# SP_proto.net
KiCad netlist of a schematic drawn in EAGLE
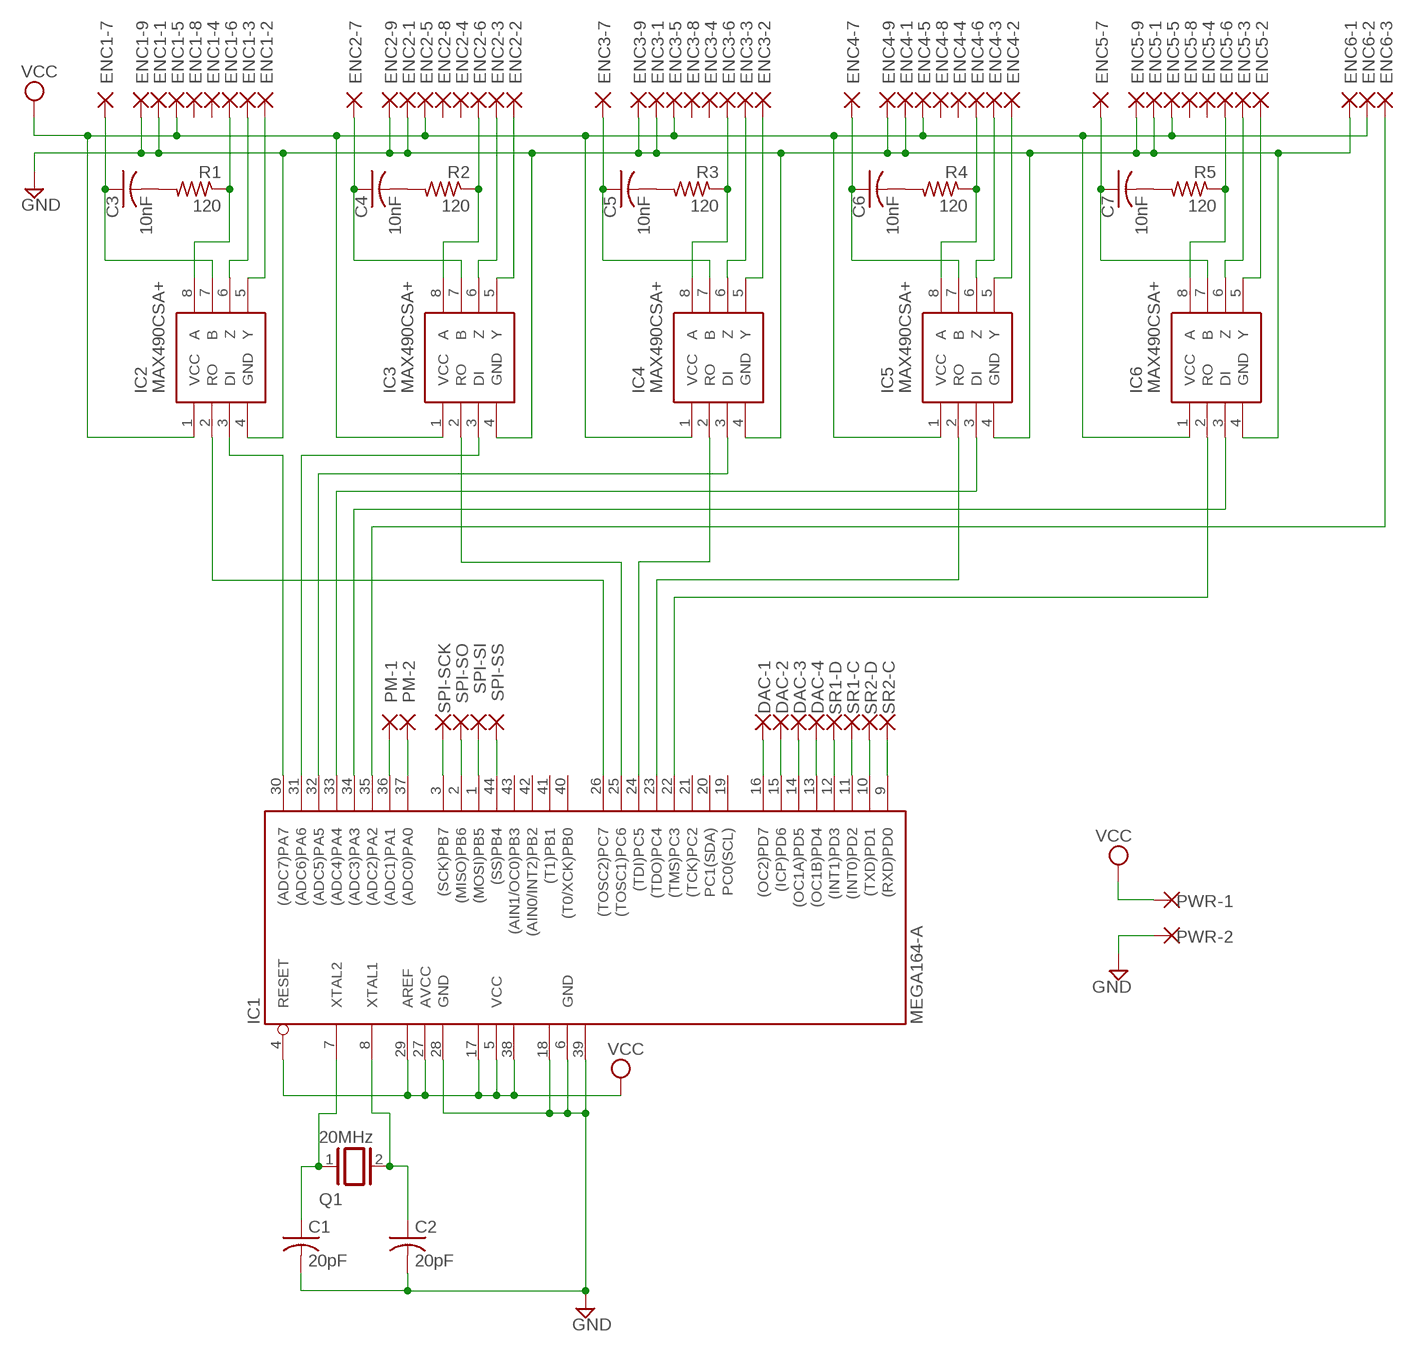
[diagram p0: schematic, sheet 1]

(export (version "E")
  (design (tool "Eeschema 10.0.6"))
  (components
    (comp (ref "C1")
      (value "20pF")
      (footprint "eagle-import:C050-024X044")
      (libsource (lib "eagle-import") (part "C-US050-024X044"))
    )
    (comp (ref "C2")
      (value "20pF")
      (footprint "eagle-import:C050-024X044")
      (libsource (lib "eagle-import") (part "C-US050-024X044"))
    )
    (comp (ref "C3")
      (value "10nF")
      (footprint "eagle-import:C050-024X044")
      (libsource (lib "eagle-import") (part "C-US050-024X044"))
    )
    (comp (ref "C4")
      (value "10nF")
      (footprint "eagle-import:C050-024X044")
      (libsource (lib "eagle-import") (part "C-US050-024X044"))
    )
    (comp (ref "C5")
      (value "10nF")
      (footprint "eagle-import:C050-024X044")
      (libsource (lib "eagle-import") (part "C-US050-024X044"))
    )
    (comp (ref "C6")
      (value "10nF")
      (footprint "eagle-import:C050-024X044")
      (libsource (lib "eagle-import") (part "C-US050-024X044"))
    )
    (comp (ref "C7")
      (value "10nF")
      (footprint "eagle-import:C050-024X044")
      (libsource (lib "eagle-import") (part "C-US050-024X044"))
    )
    (comp (ref "DAC-1")
      (value "1,6/0,8")
      (footprint "eagle-import:1,6_0,8")
      (libsource (lib "eagle-import") (part "1,6/0,8"))
    )
    (comp (ref "DAC-2")
      (value "1,6/0,8")
      (footprint "eagle-import:1,6_0,8")
      (libsource (lib "eagle-import") (part "1,6/0,8"))
    )
    (comp (ref "DAC-3")
      (value "1,6/0,8")
      (footprint "eagle-import:1,6_0,8")
      (libsource (lib "eagle-import") (part "1,6/0,8"))
    )
    (comp (ref "DAC-4")
      (value "1,6/0,8")
      (footprint "eagle-import:1,6_0,8")
      (libsource (lib "eagle-import") (part "1,6/0,8"))
    )
    (comp (ref "ENC1-1")
      (value "1,6/0,8")
      (footprint "eagle-import:1,6_0,8")
      (libsource (lib "eagle-import") (part "1,6/0,8"))
    )
    (comp (ref "ENC1-2")
      (value "1,6/0,8")
      (footprint "eagle-import:1,6_0,8")
      (libsource (lib "eagle-import") (part "1,6/0,8"))
    )
    (comp (ref "ENC1-3")
      (value "1,6/0,8")
      (footprint "eagle-import:1,6_0,8")
      (libsource (lib "eagle-import") (part "1,6/0,8"))
    )
    (comp (ref "ENC1-4")
      (value "1,6/0,8")
      (footprint "eagle-import:1,6_0,8")
      (libsource (lib "eagle-import") (part "1,6/0,8"))
    )
    (comp (ref "ENC1-5")
      (value "1,6/0,8")
      (footprint "eagle-import:1,6_0,8")
      (libsource (lib "eagle-import") (part "1,6/0,8"))
    )
    (comp (ref "ENC1-6")
      (value "1,6/0,8")
      (footprint "eagle-import:1,6_0,8")
      (libsource (lib "eagle-import") (part "1,6/0,8"))
    )
    (comp (ref "ENC1-7")
      (value "1,6/0,8")
      (footprint "eagle-import:1,6_0,8")
      (libsource (lib "eagle-import") (part "1,6/0,8"))
    )
    (comp (ref "ENC1-8")
      (value "1,6/0,8")
      (footprint "eagle-import:1,6_0,8")
      (libsource (lib "eagle-import") (part "1,6/0,8"))
    )
    (comp (ref "ENC1-9")
      (value "1,6/0,8")
      (footprint "eagle-import:1,6_0,8")
      (libsource (lib "eagle-import") (part "1,6/0,8"))
    )
    (comp (ref "ENC2-1")
      (value "1,6/0,8")
      (footprint "eagle-import:1,6_0,8")
      (libsource (lib "eagle-import") (part "1,6/0,8"))
    )
    (comp (ref "ENC2-2")
      (value "1,6/0,8")
      (footprint "eagle-import:1,6_0,8")
      (libsource (lib "eagle-import") (part "1,6/0,8"))
    )
    (comp (ref "ENC2-3")
      (value "1,6/0,8")
      (footprint "eagle-import:1,6_0,8")
      (libsource (lib "eagle-import") (part "1,6/0,8"))
    )
    (comp (ref "ENC2-4")
      (value "1,6/0,8")
      (footprint "eagle-import:1,6_0,8")
      (libsource (lib "eagle-import") (part "1,6/0,8"))
    )
    (comp (ref "ENC2-5")
      (value "1,6/0,8")
      (footprint "eagle-import:1,6_0,8")
      (libsource (lib "eagle-import") (part "1,6/0,8"))
    )
    (comp (ref "ENC2-6")
      (value "1,6/0,8")
      (footprint "eagle-import:1,6_0,8")
      (libsource (lib "eagle-import") (part "1,6/0,8"))
    )
    (comp (ref "ENC2-7")
      (value "1,6/0,8")
      (footprint "eagle-import:1,6_0,8")
      (libsource (lib "eagle-import") (part "1,6/0,8"))
    )
    (comp (ref "ENC2-8")
      (value "1,6/0,8")
      (footprint "eagle-import:1,6_0,8")
      (libsource (lib "eagle-import") (part "1,6/0,8"))
    )
    (comp (ref "ENC2-9")
      (value "1,6/0,8")
      (footprint "eagle-import:1,6_0,8")
      (libsource (lib "eagle-import") (part "1,6/0,8"))
    )
    (comp (ref "ENC3-1")
      (value "1,6/0,8")
      (footprint "eagle-import:1,6_0,8")
      (libsource (lib "eagle-import") (part "1,6/0,8"))
    )
    (comp (ref "ENC3-2")
      (value "1,6/0,8")
      (footprint "eagle-import:1,6_0,8")
      (libsource (lib "eagle-import") (part "1,6/0,8"))
    )
    (comp (ref "ENC3-3")
      (value "1,6/0,8")
      (footprint "eagle-import:1,6_0,8")
      (libsource (lib "eagle-import") (part "1,6/0,8"))
    )
    (comp (ref "ENC3-4")
      (value "1,6/0,8")
      (footprint "eagle-import:1,6_0,8")
      (libsource (lib "eagle-import") (part "1,6/0,8"))
    )
    (comp (ref "ENC3-5")
      (value "1,6/0,8")
      (footprint "eagle-import:1,6_0,8")
      (libsource (lib "eagle-import") (part "1,6/0,8"))
    )
    (comp (ref "ENC3-6")
      (value "1,6/0,8")
      (footprint "eagle-import:1,6_0,8")
      (libsource (lib "eagle-import") (part "1,6/0,8"))
    )
    (comp (ref "ENC3-7")
      (value "1,6/0,8")
      (footprint "eagle-import:1,6_0,8")
      (libsource (lib "eagle-import") (part "1,6/0,8"))
    )
    (comp (ref "ENC3-8")
      (value "1,6/0,8")
      (footprint "eagle-import:1,6_0,8")
      (libsource (lib "eagle-import") (part "1,6/0,8"))
    )
    (comp (ref "ENC3-9")
      (value "1,6/0,8")
      (footprint "eagle-import:1,6_0,8")
      (libsource (lib "eagle-import") (part "1,6/0,8"))
    )
    (comp (ref "ENC4-1")
      (value "1,6/0,8")
      (footprint "eagle-import:1,6_0,8")
      (libsource (lib "eagle-import") (part "1,6/0,8"))
    )
    (comp (ref "ENC4-2")
      (value "1,6/0,8")
      (footprint "eagle-import:1,6_0,8")
      (libsource (lib "eagle-import") (part "1,6/0,8"))
    )
    (comp (ref "ENC4-3")
      (value "1,6/0,8")
      (footprint "eagle-import:1,6_0,8")
      (libsource (lib "eagle-import") (part "1,6/0,8"))
    )
    (comp (ref "ENC4-4")
      (value "1,6/0,8")
      (footprint "eagle-import:1,6_0,8")
      (libsource (lib "eagle-import") (part "1,6/0,8"))
    )
    (comp (ref "ENC4-5")
      (value "1,6/0,8")
      (footprint "eagle-import:1,6_0,8")
      (libsource (lib "eagle-import") (part "1,6/0,8"))
    )
    (comp (ref "ENC4-6")
      (value "1,6/0,8")
      (footprint "eagle-import:1,6_0,8")
      (libsource (lib "eagle-import") (part "1,6/0,8"))
    )
    (comp (ref "ENC4-7")
      (value "1,6/0,8")
      (footprint "eagle-import:1,6_0,8")
      (libsource (lib "eagle-import") (part "1,6/0,8"))
    )
    (comp (ref "ENC4-8")
      (value "1,6/0,8")
      (footprint "eagle-import:1,6_0,8")
      (libsource (lib "eagle-import") (part "1,6/0,8"))
    )
    (comp (ref "ENC4-9")
      (value "1,6/0,8")
      (footprint "eagle-import:1,6_0,8")
      (libsource (lib "eagle-import") (part "1,6/0,8"))
    )
    (comp (ref "ENC5-1")
      (value "1,6/0,8")
      (footprint "eagle-import:1,6_0,8")
      (libsource (lib "eagle-import") (part "1,6/0,8"))
    )
    (comp (ref "ENC5-2")
      (value "1,6/0,8")
      (footprint "eagle-import:1,6_0,8")
      (libsource (lib "eagle-import") (part "1,6/0,8"))
    )
    (comp (ref "ENC5-3")
      (value "1,6/0,8")
      (footprint "eagle-import:1,6_0,8")
      (libsource (lib "eagle-import") (part "1,6/0,8"))
    )
    (comp (ref "ENC5-4")
      (value "1,6/0,8")
      (footprint "eagle-import:1,6_0,8")
      (libsource (lib "eagle-import") (part "1,6/0,8"))
    )
    (comp (ref "ENC5-5")
      (value "1,6/0,8")
      (footprint "eagle-import:1,6_0,8")
      (libsource (lib "eagle-import") (part "1,6/0,8"))
    )
    (comp (ref "ENC5-6")
      (value "1,6/0,8")
      (footprint "eagle-import:1,6_0,8")
      (libsource (lib "eagle-import") (part "1,6/0,8"))
    )
    (comp (ref "ENC5-7")
      (value "1,6/0,8")
      (footprint "eagle-import:1,6_0,8")
      (libsource (lib "eagle-import") (part "1,6/0,8"))
    )
    (comp (ref "ENC5-8")
      (value "1,6/0,8")
      (footprint "eagle-import:1,6_0,8")
      (libsource (lib "eagle-import") (part "1,6/0,8"))
    )
    (comp (ref "ENC5-9")
      (value "1,6/0,8")
      (footprint "eagle-import:1,6_0,8")
      (libsource (lib "eagle-import") (part "1,6/0,8"))
    )
    (comp (ref "ENC6-1")
      (value "1,6/0,8")
      (footprint "eagle-import:1,6_0,8")
      (libsource (lib "eagle-import") (part "1,6/0,8"))
    )
    (comp (ref "ENC6-2")
      (value "1,6/0,8")
      (footprint "eagle-import:1,6_0,8")
      (libsource (lib "eagle-import") (part "1,6/0,8"))
    )
    (comp (ref "ENC6-3")
      (value "1,6/0,8")
      (footprint "eagle-import:1,6_0,8")
      (libsource (lib "eagle-import") (part "1,6/0,8"))
    )
    (comp (ref "IC1")
      (value "MEGA164-A")
      (footprint "eagle-import:TQFP44")
      (fields (field (name "MPN") "ATMEGA16-16AU"))
      (libsource (lib "eagle-import") (part "MEGA16-A"))
    )
    (comp (ref "IC2")
      (value "MAX490CSA+")
      (footprint "eagle-import:SOIC127P600X175-8N")
      (fields (field (name "RS_PART_NUMBER") "6228181P"))
      (libsource (lib "eagle-import") (part "MAX490CSA+"))
    )
    (comp (ref "IC3")
      (value "MAX490CSA+")
      (footprint "eagle-import:SOIC127P600X175-8N")
      (fields (field (name "RS_PART_NUMBER") "6228181P"))
      (libsource (lib "eagle-import") (part "MAX490CSA+"))
    )
    (comp (ref "IC4")
      (value "MAX490CSA+")
      (footprint "eagle-import:SOIC127P600X175-8N")
      (fields (field (name "RS_PART_NUMBER") "6228181P"))
      (libsource (lib "eagle-import") (part "MAX490CSA+"))
    )
    (comp (ref "IC5")
      (value "MAX490CSA+")
      (footprint "eagle-import:SOIC127P600X175-8N")
      (fields (field (name "RS_PART_NUMBER") "6228181P"))
      (libsource (lib "eagle-import") (part "MAX490CSA+"))
    )
    (comp (ref "IC6")
      (value "MAX490CSA+")
      (footprint "eagle-import:SOIC127P600X175-8N")
      (fields (field (name "RS_PART_NUMBER") "6228181P"))
      (libsource (lib "eagle-import") (part "MAX490CSA+"))
    )
    (comp (ref "PM-1")
      (value "1,6/0,8")
      (footprint "eagle-import:1,6_0,8")
      (libsource (lib "eagle-import") (part "1,6/0,8"))
    )
    (comp (ref "PM-2")
      (value "1,6/0,8")
      (footprint "eagle-import:1,6_0,8")
      (libsource (lib "eagle-import") (part "1,6/0,8"))
    )
    (comp (ref "PWR-1")
      (value "1,6/0,8")
      (footprint "eagle-import:1,6_0,8")
      (libsource (lib "eagle-import") (part "1,6/0,8"))
    )
    (comp (ref "PWR-2")
      (value "1,6/0,8")
      (footprint "eagle-import:1,6_0,8")
      (libsource (lib "eagle-import") (part "1,6/0,8"))
    )
    (comp (ref "Q1")
      (value "20MHz")
      (footprint "eagle-import:QS")
      (libsource (lib "eagle-import") (part "XTAL/S"))
    )
    (comp (ref "R1")
      (value "120")
      (footprint "eagle-import:0204_7")
      (libsource (lib "eagle-import") (part "R-US_0204/7"))
    )
    (comp (ref "R2")
      (value "120")
      (footprint "eagle-import:0204_7")
      (libsource (lib "eagle-import") (part "R-US_0204/7"))
    )
    (comp (ref "R3")
      (value "120")
      (footprint "eagle-import:0204_7")
      (libsource (lib "eagle-import") (part "R-US_0204/7"))
    )
    (comp (ref "R4")
      (value "120")
      (footprint "eagle-import:0204_7")
      (libsource (lib "eagle-import") (part "R-US_0204/7"))
    )
    (comp (ref "R5")
      (value "120")
      (footprint "eagle-import:0204_7")
      (libsource (lib "eagle-import") (part "R-US_0204/7"))
    )
    (comp (ref "SPI-SCK")
      (value "1,6/0,8")
      (footprint "eagle-import:1,6_0,8")
      (libsource (lib "eagle-import") (part "1,6/0,8"))
    )
    (comp (ref "SPI-SI")
      (value "1,6/0,8")
      (footprint "eagle-import:1,6_0,8")
      (libsource (lib "eagle-import") (part "1,6/0,8"))
    )
    (comp (ref "SPI-SO")
      (value "1,6/0,8")
      (footprint "eagle-import:1,6_0,8")
      (libsource (lib "eagle-import") (part "1,6/0,8"))
    )
    (comp (ref "SPI-SS")
      (value "1,6/0,8")
      (footprint "eagle-import:1,6_0,8")
      (libsource (lib "eagle-import") (part "1,6/0,8"))
    )
    (comp (ref "SR1-C")
      (value "1,6/0,8")
      (footprint "eagle-import:1,6_0,8")
      (libsource (lib "eagle-import") (part "1,6/0,8"))
    )
    (comp (ref "SR1-D")
      (value "1,6/0,8")
      (footprint "eagle-import:1,6_0,8")
      (libsource (lib "eagle-import") (part "1,6/0,8"))
    )
    (comp (ref "SR2-C")
      (value "1,6/0,8")
      (footprint "eagle-import:1,6_0,8")
      (libsource (lib "eagle-import") (part "1,6/0,8"))
    )
    (comp (ref "SR2-D")
      (value "1,6/0,8")
      (footprint "eagle-import:1,6_0,8")
      (libsource (lib "eagle-import") (part "1,6/0,8"))
    )
  )
  (nets
    (net (code "1") (name "GND") (class "Default")
      (node (ref "C1") (pin "2") (pinfunction "2_2") (pintype "passive"))
      (node (ref "C2") (pin "2") (pinfunction "2_2") (pintype "passive"))
      (node (ref "ENC1-1") (pin "1") (pinfunction "P_1") (pintype "passive"))
      (node (ref "ENC1-9") (pin "1") (pinfunction "P_1") (pintype "passive"))
      (node (ref "ENC2-1") (pin "1") (pinfunction "P_1") (pintype "passive"))
      (node (ref "ENC2-9") (pin "1") (pinfunction "P_1") (pintype "passive"))
      (node (ref "ENC3-1") (pin "1") (pinfunction "P_1") (pintype "passive"))
      (node (ref "ENC3-9") (pin "1") (pinfunction "P_1") (pintype "passive"))
      (node (ref "ENC4-1") (pin "1") (pinfunction "P_1") (pintype "passive"))
      (node (ref "ENC4-9") (pin "1") (pinfunction "P_1") (pintype "passive"))
      (node (ref "ENC5-1") (pin "1") (pinfunction "P_1") (pintype "passive"))
      (node (ref "ENC5-9") (pin "1") (pinfunction "P_1") (pintype "passive"))
      (node (ref "ENC6-1") (pin "1") (pinfunction "P_1") (pintype "passive"))
      (node (ref "IC1") (pin "18") (pinfunction "GND1_18") (pintype "power_in"))
      (node (ref "IC1") (pin "28") (pinfunction "GND_28") (pintype "power_in"))
      (node (ref "IC1") (pin "39") (pinfunction "GND2_39") (pintype "power_in"))
      (node (ref "IC1") (pin "6") (pinfunction "GND_6") (pintype "power_in"))
      (node (ref "IC2") (pin "4") (pinfunction "GND_4") (pintype "power_in"))
      (node (ref "IC3") (pin "4") (pinfunction "GND_4") (pintype "power_in"))
      (node (ref "IC4") (pin "4") (pinfunction "GND_4") (pintype "power_in"))
      (node (ref "IC5") (pin "4") (pinfunction "GND_4") (pintype "power_in"))
      (node (ref "IC6") (pin "4") (pinfunction "GND_4") (pintype "power_in"))
      (node (ref "PWR-2") (pin "1") (pinfunction "P_1") (pintype "passive"))
    )
    (net (code "2") (name "Net-(C3-Pad2)") (class "Default")
      (node (ref "C3") (pin "2") (pinfunction "2_2") (pintype "passive"))
      (node (ref "R1") (pin "2") (pinfunction "2_2") (pintype "passive"))
    )
    (net (code "3") (name "Net-(C4-Pad2)") (class "Default")
      (node (ref "C4") (pin "2") (pinfunction "2_2") (pintype "passive"))
      (node (ref "R2") (pin "2") (pinfunction "2_2") (pintype "passive"))
    )
    (net (code "4") (name "Net-(C5-Pad2)") (class "Default")
      (node (ref "C5") (pin "2") (pinfunction "2_2") (pintype "passive"))
      (node (ref "R3") (pin "2") (pinfunction "2_2") (pintype "passive"))
    )
    (net (code "5") (name "Net-(C6-Pad2)") (class "Default")
      (node (ref "C6") (pin "2") (pinfunction "2_2") (pintype "passive"))
      (node (ref "R4") (pin "2") (pinfunction "2_2") (pintype "passive"))
    )
    (net (code "6") (name "Net-(C7-Pad2)") (class "Default")
      (node (ref "C7") (pin "2") (pinfunction "2_2") (pintype "passive"))
      (node (ref "R5") (pin "2") (pinfunction "2_2") (pintype "passive"))
    )
    (net (code "7") (name "Net-(DAC-1-P)") (class "Default")
      (node (ref "DAC-1") (pin "1") (pinfunction "P_1") (pintype "passive"))
      (node (ref "IC1") (pin "16") (pinfunction "(OC2)PD7_16") (pintype "bidirectional"))
    )
    (net (code "8") (name "Net-(DAC-2-P)") (class "Default")
      (node (ref "DAC-2") (pin "1") (pinfunction "P_1") (pintype "passive"))
      (node (ref "IC1") (pin "15") (pinfunction "(ICP)PD6_15") (pintype "bidirectional"))
    )
    (net (code "9") (name "Net-(DAC-3-P)") (class "Default")
      (node (ref "DAC-3") (pin "1") (pinfunction "P_1") (pintype "passive"))
      (node (ref "IC1") (pin "14") (pinfunction "(OC1A)PD5_14") (pintype "bidirectional"))
    )
    (net (code "10") (name "Net-(DAC-4-P)") (class "Default")
      (node (ref "DAC-4") (pin "1") (pinfunction "P_1") (pintype "passive"))
      (node (ref "IC1") (pin "13") (pinfunction "(OC1B)PD4_13") (pintype "bidirectional"))
    )
    (net (code "11") (name "Net-(ENC1-2-P)") (class "Default")
      (node (ref "ENC1-2") (pin "1") (pinfunction "P_1") (pintype "passive"))
      (node (ref "IC2") (pin "5") (pinfunction "Y_5") (pintype "bidirectional"))
    )
    (net (code "12") (name "Net-(ENC1-3-P)") (class "Default")
      (node (ref "ENC1-3") (pin "1") (pinfunction "P_1") (pintype "passive"))
      (node (ref "IC2") (pin "6") (pinfunction "Z_6") (pintype "bidirectional"))
    )
    (net (code "13") (name "Net-(ENC1-6-P)") (class "Default")
      (node (ref "ENC1-6") (pin "1") (pinfunction "P_1") (pintype "passive"))
      (node (ref "IC2") (pin "8") (pinfunction "A_8") (pintype "bidirectional"))
      (node (ref "R1") (pin "1") (pinfunction "1_1") (pintype "passive"))
    )
    (net (code "14") (name "Net-(ENC1-7-P)") (class "Default")
      (node (ref "C3") (pin "1") (pinfunction "1_1") (pintype "passive"))
      (node (ref "ENC1-7") (pin "1") (pinfunction "P_1") (pintype "passive"))
      (node (ref "IC2") (pin "7") (pinfunction "B_7") (pintype "bidirectional"))
    )
    (net (code "15") (name "Net-(ENC2-2-P)") (class "Default")
      (node (ref "ENC2-2") (pin "1") (pinfunction "P_1") (pintype "passive"))
      (node (ref "IC3") (pin "5") (pinfunction "Y_5") (pintype "bidirectional"))
    )
    (net (code "16") (name "Net-(ENC2-3-P)") (class "Default")
      (node (ref "ENC2-3") (pin "1") (pinfunction "P_1") (pintype "passive"))
      (node (ref "IC3") (pin "6") (pinfunction "Z_6") (pintype "bidirectional"))
    )
    (net (code "17") (name "Net-(ENC2-6-P)") (class "Default")
      (node (ref "ENC2-6") (pin "1") (pinfunction "P_1") (pintype "passive"))
      (node (ref "IC3") (pin "8") (pinfunction "A_8") (pintype "bidirectional"))
      (node (ref "R2") (pin "1") (pinfunction "1_1") (pintype "passive"))
    )
    (net (code "18") (name "Net-(ENC2-7-P)") (class "Default")
      (node (ref "C4") (pin "1") (pinfunction "1_1") (pintype "passive"))
      (node (ref "ENC2-7") (pin "1") (pinfunction "P_1") (pintype "passive"))
      (node (ref "IC3") (pin "7") (pinfunction "B_7") (pintype "bidirectional"))
    )
    (net (code "19") (name "Net-(ENC3-2-P)") (class "Default")
      (node (ref "ENC3-2") (pin "1") (pinfunction "P_1") (pintype "passive"))
      (node (ref "IC4") (pin "5") (pinfunction "Y_5") (pintype "bidirectional"))
    )
    (net (code "20") (name "Net-(ENC3-3-P)") (class "Default")
      (node (ref "ENC3-3") (pin "1") (pinfunction "P_1") (pintype "passive"))
      (node (ref "IC4") (pin "6") (pinfunction "Z_6") (pintype "bidirectional"))
    )
    (net (code "21") (name "Net-(ENC3-6-P)") (class "Default")
      (node (ref "ENC3-6") (pin "1") (pinfunction "P_1") (pintype "passive"))
      (node (ref "IC4") (pin "8") (pinfunction "A_8") (pintype "bidirectional"))
      (node (ref "R3") (pin "1") (pinfunction "1_1") (pintype "passive"))
    )
    (net (code "22") (name "Net-(ENC3-7-P)") (class "Default")
      (node (ref "C5") (pin "1") (pinfunction "1_1") (pintype "passive"))
      (node (ref "ENC3-7") (pin "1") (pinfunction "P_1") (pintype "passive"))
      (node (ref "IC4") (pin "7") (pinfunction "B_7") (pintype "bidirectional"))
    )
    (net (code "23") (name "Net-(ENC4-2-P)") (class "Default")
      (node (ref "ENC4-2") (pin "1") (pinfunction "P_1") (pintype "passive"))
      (node (ref "IC5") (pin "5") (pinfunction "Y_5") (pintype "bidirectional"))
    )
    (net (code "24") (name "Net-(ENC4-3-P)") (class "Default")
      (node (ref "ENC4-3") (pin "1") (pinfunction "P_1") (pintype "passive"))
      (node (ref "IC5") (pin "6") (pinfunction "Z_6") (pintype "bidirectional"))
    )
    (net (code "25") (name "Net-(ENC4-6-P)") (class "Default")
      (node (ref "ENC4-6") (pin "1") (pinfunction "P_1") (pintype "passive"))
      (node (ref "IC5") (pin "8") (pinfunction "A_8") (pintype "bidirectional"))
      (node (ref "R4") (pin "1") (pinfunction "1_1") (pintype "passive"))
    )
    (net (code "26") (name "Net-(ENC4-7-P)") (class "Default")
      (node (ref "C6") (pin "1") (pinfunction "1_1") (pintype "passive"))
      (node (ref "ENC4-7") (pin "1") (pinfunction "P_1") (pintype "passive"))
      (node (ref "IC5") (pin "7") (pinfunction "B_7") (pintype "bidirectional"))
    )
    (net (code "27") (name "Net-(ENC5-2-P)") (class "Default")
      (node (ref "ENC5-2") (pin "1") (pinfunction "P_1") (pintype "passive"))
      (node (ref "IC6") (pin "5") (pinfunction "Y_5") (pintype "bidirectional"))
    )
    (net (code "28") (name "Net-(ENC5-3-P)") (class "Default")
      (node (ref "ENC5-3") (pin "1") (pinfunction "P_1") (pintype "passive"))
      (node (ref "IC6") (pin "6") (pinfunction "Z_6") (pintype "bidirectional"))
    )
    (net (code "29") (name "Net-(ENC5-6-P)") (class "Default")
      (node (ref "ENC5-6") (pin "1") (pinfunction "P_1") (pintype "passive"))
      (node (ref "IC6") (pin "8") (pinfunction "A_8") (pintype "bidirectional"))
      (node (ref "R5") (pin "1") (pinfunction "1_1") (pintype "passive"))
    )
    (net (code "30") (name "Net-(ENC5-7-P)") (class "Default")
      (node (ref "C7") (pin "1") (pinfunction "1_1") (pintype "passive"))
      (node (ref "ENC5-7") (pin "1") (pinfunction "P_1") (pintype "passive"))
      (node (ref "IC6") (pin "7") (pinfunction "B_7") (pintype "bidirectional"))
    )
    (net (code "31") (name "Net-(ENC6-3-P)") (class "Default")
      (node (ref "ENC6-3") (pin "1") (pinfunction "P_1") (pintype "passive"))
      (node (ref "IC1") (pin "35") (pinfunction "(ADC2)PA2_35") (pintype "bidirectional"))
    )
    (net (code "32") (name "Net-(IC1-(ADC0)PA0)") (class "Default")
      (node (ref "IC1") (pin "37") (pinfunction "(ADC0)PA0_37") (pintype "bidirectional"))
      (node (ref "PM-2") (pin "1") (pinfunction "P_1") (pintype "passive"))
    )
    (net (code "33") (name "Net-(IC1-(ADC1)PA1)") (class "Default")
      (node (ref "IC1") (pin "36") (pinfunction "(ADC1)PA1_36") (pintype "bidirectional"))
      (node (ref "PM-1") (pin "1") (pinfunction "P_1") (pintype "passive"))
    )
    (net (code "34") (name "Net-(IC1-(ADC3)PA3)") (class "Default")
      (node (ref "IC1") (pin "34") (pinfunction "(ADC3)PA3_34") (pintype "bidirectional"))
      (node (ref "IC6") (pin "3") (pinfunction "DI_3") (pintype "bidirectional"))
    )
    (net (code "35") (name "Net-(IC1-(ADC4)PA4)") (class "Default")
      (node (ref "IC1") (pin "33") (pinfunction "(ADC4)PA4_33") (pintype "bidirectional"))
      (node (ref "IC5") (pin "3") (pinfunction "DI_3") (pintype "bidirectional"))
    )
    (net (code "36") (name "Net-(IC1-(ADC5)PA5)") (class "Default")
      (node (ref "IC1") (pin "32") (pinfunction "(ADC5)PA5_32") (pintype "bidirectional"))
      (node (ref "IC4") (pin "3") (pinfunction "DI_3") (pintype "bidirectional"))
    )
    (net (code "37") (name "Net-(IC1-(ADC6)PA6)") (class "Default")
      (node (ref "IC1") (pin "31") (pinfunction "(ADC6)PA6_31") (pintype "bidirectional"))
      (node (ref "IC3") (pin "3") (pinfunction "DI_3") (pintype "bidirectional"))
    )
    (net (code "38") (name "Net-(IC1-(ADC7)PA7)") (class "Default")
      (node (ref "IC1") (pin "30") (pinfunction "(ADC7)PA7_30") (pintype "bidirectional"))
      (node (ref "IC2") (pin "3") (pinfunction "DI_3") (pintype "bidirectional"))
    )
    (net (code "39") (name "Net-(IC1-(INT0)PD2)") (class "Default")
      (node (ref "IC1") (pin "11") (pinfunction "(INT0)PD2_11") (pintype "bidirectional"))
      (node (ref "SR1-C") (pin "1") (pinfunction "P_1") (pintype "passive"))
    )
    (net (code "40") (name "Net-(IC1-(INT1)PD3)") (class "Default")
      (node (ref "IC1") (pin "12") (pinfunction "(INT1)PD3_12") (pintype "bidirectional"))
      (node (ref "SR1-D") (pin "1") (pinfunction "P_1") (pintype "passive"))
    )
    (net (code "41") (name "Net-(IC1-(MISO)PB6)") (class "Default")
      (node (ref "IC1") (pin "2") (pinfunction "(MISO)PB6_2") (pintype "bidirectional"))
      (node (ref "SPI-SO") (pin "1") (pinfunction "P_1") (pintype "passive"))
    )
    (net (code "42") (name "Net-(IC1-(MOSI)PB5)") (class "Default")
      (node (ref "IC1") (pin "1") (pinfunction "(MOSI)PB5_1") (pintype "bidirectional"))
      (node (ref "SPI-SI") (pin "1") (pinfunction "P_1") (pintype "passive"))
    )
    (net (code "43") (name "Net-(IC1-(RXD)PD0)") (class "Default")
      (node (ref "IC1") (pin "9") (pinfunction "(RXD)PD0_9") (pintype "bidirectional"))
      (node (ref "SR2-C") (pin "1") (pinfunction "P_1") (pintype "passive"))
    )
    (net (code "44") (name "Net-(IC1-(SCK)PB7)") (class "Default")
      (node (ref "IC1") (pin "3") (pinfunction "(SCK)PB7_3") (pintype "bidirectional"))
      (node (ref "SPI-SCK") (pin "1") (pinfunction "P_1") (pintype "passive"))
    )
    (net (code "45") (name "Net-(IC1-(SS)PB4)") (class "Default")
      (node (ref "IC1") (pin "44") (pinfunction "(SS)PB4_44") (pintype "bidirectional"))
      (node (ref "SPI-SS") (pin "1") (pinfunction "P_1") (pintype "passive"))
    )
    (net (code "46") (name "Net-(IC1-(TDI)PC5)") (class "Default")
      (node (ref "IC1") (pin "24") (pinfunction "(TDI)PC5_24") (pintype "bidirectional"))
      (node (ref "IC4") (pin "2") (pinfunction "RO_2") (pintype "bidirectional"))
    )
    (net (code "47") (name "Net-(IC1-(TDO)PC4)") (class "Default")
      (node (ref "IC1") (pin "23") (pinfunction "(TDO)PC4_23") (pintype "bidirectional"))
      (node (ref "IC5") (pin "2") (pinfunction "RO_2") (pintype "bidirectional"))
    )
    (net (code "48") (name "Net-(IC1-(TMS)PC3)") (class "Default")
      (node (ref "IC1") (pin "22") (pinfunction "(TMS)PC3_22") (pintype "bidirectional"))
      (node (ref "IC6") (pin "2") (pinfunction "RO_2") (pintype "bidirectional"))
    )
    (net (code "49") (name "Net-(IC1-(TOSC1)PC6)") (class "Default")
      (node (ref "IC1") (pin "25") (pinfunction "(TOSC1)PC6_25") (pintype "bidirectional"))
      (node (ref "IC3") (pin "2") (pinfunction "RO_2") (pintype "bidirectional"))
    )
    (net (code "50") (name "Net-(IC1-(TOSC2)PC7)") (class "Default")
      (node (ref "IC1") (pin "26") (pinfunction "(TOSC2)PC7_26") (pintype "bidirectional"))
      (node (ref "IC2") (pin "2") (pinfunction "RO_2") (pintype "bidirectional"))
    )
    (net (code "51") (name "Net-(IC1-(TXD)PD1)") (class "Default")
      (node (ref "IC1") (pin "10") (pinfunction "(TXD)PD1_10") (pintype "bidirectional"))
      (node (ref "SR2-D") (pin "1") (pinfunction "P_1") (pintype "passive"))
    )
    (net (code "52") (name "Net-(IC1-XTAL1)") (class "Default")
      (node (ref "C2") (pin "1") (pinfunction "1_1") (pintype "passive"))
      (node (ref "IC1") (pin "8") (pinfunction "XTAL1_8") (pintype "bidirectional"))
      (node (ref "Q1") (pin "2") (pinfunction "2_2") (pintype "passive"))
    )
    (net (code "53") (name "Net-(IC1-XTAL2)") (class "Default")
      (node (ref "C1") (pin "1") (pinfunction "1_1") (pintype "passive"))
      (node (ref "IC1") (pin "7") (pinfunction "XTAL2_7") (pintype "bidirectional"))
      (node (ref "Q1") (pin "1") (pinfunction "1_1") (pintype "passive"))
    )
    (net (code "54") (name "VCC") (class "Default")
      (node (ref "ENC1-5") (pin "1") (pinfunction "P_1") (pintype "passive"))
      (node (ref "ENC2-5") (pin "1") (pinfunction "P_1") (pintype "passive"))
      (node (ref "ENC3-5") (pin "1") (pinfunction "P_1") (pintype "passive"))
      (node (ref "ENC4-5") (pin "1") (pinfunction "P_1") (pintype "passive"))
      (node (ref "ENC5-5") (pin "1") (pinfunction "P_1") (pintype "passive"))
      (node (ref "ENC6-2") (pin "1") (pinfunction "P_1") (pintype "passive"))
      (node (ref "IC1") (pin "17") (pinfunction "VCC1_17") (pintype "power_in"))
      (node (ref "IC1") (pin "27") (pinfunction "AVCC_27") (pintype "power_in"))
      (node (ref "IC1") (pin "29") (pinfunction "AREF_29") (pintype "passive"))
      (node (ref "IC1") (pin "38") (pinfunction "VCC2_38") (pintype "power_in"))
      (node (ref "IC1") (pin "4") (pinfunction "RESET_4") (pintype "input"))
      (node (ref "IC1") (pin "5") (pinfunction "VCC_5") (pintype "power_in"))
      (node (ref "IC2") (pin "1") (pinfunction "VCC_1") (pintype "power_in"))
      (node (ref "IC3") (pin "1") (pinfunction "VCC_1") (pintype "power_in"))
      (node (ref "IC4") (pin "1") (pinfunction "VCC_1") (pintype "power_in"))
      (node (ref "IC5") (pin "1") (pinfunction "VCC_1") (pintype "power_in"))
      (node (ref "IC6") (pin "1") (pinfunction "VCC_1") (pintype "power_in"))
      (node (ref "PWR-1") (pin "1") (pinfunction "P_1") (pintype "passive"))
    )
    (net (code "55") (name "unconnected-(ENC1-4-P-Pad1)") (class "Default")
      (node (ref "ENC1-4") (pin "1") (pinfunction "P_1") (pintype "passive"))
    )
    (net (code "56") (name "unconnected-(ENC1-8-P-Pad1)") (class "Default")
      (node (ref "ENC1-8") (pin "1") (pinfunction "P_1") (pintype "passive"))
    )
    (net (code "57") (name "unconnected-(ENC2-4-P-Pad1)") (class "Default")
      (node (ref "ENC2-4") (pin "1") (pinfunction "P_1") (pintype "passive"))
    )
    (net (code "58") (name "unconnected-(ENC2-8-P-Pad1)") (class "Default")
      (node (ref "ENC2-8") (pin "1") (pinfunction "P_1") (pintype "passive"))
    )
    (net (code "59") (name "unconnected-(ENC3-4-P-Pad1)") (class "Default")
      (node (ref "ENC3-4") (pin "1") (pinfunction "P_1") (pintype "passive"))
    )
    (net (code "60") (name "unconnected-(ENC3-8-P-Pad1)") (class "Default")
      (node (ref "ENC3-8") (pin "1") (pinfunction "P_1") (pintype "passive"))
    )
    (net (code "61") (name "unconnected-(ENC4-4-P-Pad1)") (class "Default")
      (node (ref "ENC4-4") (pin "1") (pinfunction "P_1") (pintype "passive"))
    )
    (net (code "62") (name "unconnected-(ENC4-8-P-Pad1)") (class "Default")
      (node (ref "ENC4-8") (pin "1") (pinfunction "P_1") (pintype "passive"))
    )
    (net (code "63") (name "unconnected-(ENC5-4-P-Pad1)") (class "Default")
      (node (ref "ENC5-4") (pin "1") (pinfunction "P_1") (pintype "passive"))
    )
    (net (code "64") (name "unconnected-(ENC5-8-P-Pad1)") (class "Default")
      (node (ref "ENC5-8") (pin "1") (pinfunction "P_1") (pintype "passive"))
    )
    (net (code "65") (name "unconnected-(IC1-(AIN0{slash}INT2)PB2-Pad42)") (class "Default")
      (node (ref "IC1") (pin "42") (pinfunction "(AIN0/INT2)PB2_42") (pintype "bidirectional"))
    )
    (net (code "66") (name "unconnected-(IC1-(AIN1{slash}OC0)PB3-Pad43)") (class "Default")
      (node (ref "IC1") (pin "43") (pinfunction "(AIN1/OC0)PB3_43") (pintype "bidirectional"))
    )
    (net (code "67") (name "unconnected-(IC1-(T0{slash}XCK)PB0-Pad40)") (class "Default")
      (node (ref "IC1") (pin "40") (pinfunction "(T0/XCK)PB0_40") (pintype "bidirectional"))
    )
    (net (code "68") (name "unconnected-(IC1-(T1)PB1-Pad41)") (class "Default")
      (node (ref "IC1") (pin "41") (pinfunction "(T1)PB1_41") (pintype "bidirectional"))
    )
    (net (code "69") (name "unconnected-(IC1-(TCK)PC2-Pad21)") (class "Default")
      (node (ref "IC1") (pin "21") (pinfunction "(TCK)PC2_21") (pintype "bidirectional"))
    )
    (net (code "70") (name "unconnected-(IC1-PC0(SCL)-Pad19)") (class "Default")
      (node (ref "IC1") (pin "19") (pinfunction "PC0(SCL)_19") (pintype "bidirectional"))
    )
    (net (code "71") (name "unconnected-(IC1-PC1(SDA)-Pad20)") (class "Default")
      (node (ref "IC1") (pin "20") (pinfunction "PC1(SDA)_20") (pintype "bidirectional"))
    )
  )
)
